# LFO.net
KiCad netlist of a schematic drawn in EAGLE
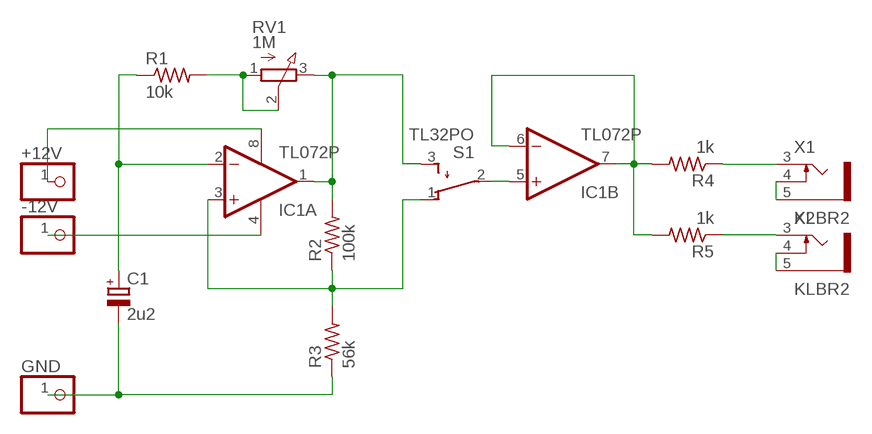
[diagram p0: schematic, sheet 1]

(export (version "E")
  (design (tool "Eeschema 10.0.6"))
  (components
    (comp (ref "+12V")
      (value "PINHD-1X1")
      (footprint "eagle-import:1X01")
      (libsource (lib "eagle-import") (part "PINHD-1X1"))
    )
    (comp (ref "-12V")
      (value "PINHD-1X1")
      (footprint "eagle-import:1X01")
      (libsource (lib "eagle-import") (part "PINHD-1X1"))
    )
    (comp (ref "C1")
      (value "2u2")
      (footprint "eagle-import:E2,5-6E")
      (libsource (lib "eagle-import") (part "CPOL-EUE2,5-6E"))
    )
    (comp (ref "GND")
      (value "PINHD-1X1")
      (footprint "eagle-import:1X01")
      (libsource (lib "eagle-import") (part "PINHD-1X1"))
    )
    (comp (ref "IC1")
      (value "TL072P")
      (footprint "eagle-import:DIL08")
      (libsource (lib "eagle-import") (part "TL072P"))
    )
    (comp (ref "R1")
      (value "10k")
      (footprint "eagle-import:0204_7")
      (libsource (lib "eagle-import") (part "R-US_0204/7"))
    )
    (comp (ref "R2")
      (value "100k")
      (footprint "eagle-import:0204_7")
      (libsource (lib "eagle-import") (part "R-US_0204/7"))
    )
    (comp (ref "R3")
      (value "56k")
      (footprint "eagle-import:0204_7")
      (libsource (lib "eagle-import") (part "R-US_0204/7"))
    )
    (comp (ref "R4")
      (value "1k")
      (footprint "eagle-import:0204_7")
      (libsource (lib "eagle-import") (part "R-US_0204/7"))
    )
    (comp (ref "R5")
      (value "1k")
      (footprint "eagle-import:0204_7")
      (libsource (lib "eagle-import") (part "R-US_0204/7"))
    )
    (comp (ref "RV1")
      (value "1M")
      (footprint "eagle-import:3RP_1610N")
      (libsource (lib "eagle-import") (part "3RP/1610N"))
    )
    (comp (ref "S1")
      (value "TL32PO")
      (footprint "eagle-import:TL3XPO")
      (libsource (lib "eagle-import") (part "TL32PO"))
    )
    (comp (ref "X1")
      (value "KLBR2")
      (footprint "eagle-import:KLBR2")
      (libsource (lib "eagle-import") (part "KLBR?2"))
    )
    (comp (ref "X2")
      (value "KLBR2")
      (footprint "eagle-import:KLBR2")
      (libsource (lib "eagle-import") (part "KLBR?2"))
    )
  )
  (nets
    (net (code "1") (name "Net-(C1-Pad-)") (class "Default")
      (node (ref "C1") (pin "-") (pinfunction "-_-") (pintype "passive"))
      (node (ref "GND") (pin "1") (pinfunction "1_1") (pintype "passive"))
      (node (ref "R3") (pin "1") (pinfunction "1_1") (pintype "passive"))
    )
    (net (code "2") (name "Net-(IC1A-+IN)") (class "Default")
      (node (ref "IC1") (pin "3") (pinfunction "+IN_3") (pintype "input"))
      (node (ref "R2") (pin "1") (pinfunction "1_1") (pintype "passive"))
      (node (ref "R3") (pin "2") (pinfunction "2_2") (pintype "passive"))
      (node (ref "S1") (pin "1") (pinfunction "O_1") (pintype "passive"))
    )
    (net (code "3") (name "Net-(IC1A--IN)") (class "Default")
      (node (ref "C1") (pin "+") (pinfunction "+_+") (pintype "passive"))
      (node (ref "IC1") (pin "2") (pinfunction "-IN_2") (pintype "input"))
      (node (ref "R1") (pin "1") (pinfunction "1_1") (pintype "passive"))
    )
    (net (code "4") (name "Net-(IC1A-OUT)") (class "Default")
      (node (ref "IC1") (pin "1") (pinfunction "OUT_1") (pintype "output"))
      (node (ref "R2") (pin "2") (pinfunction "2_2") (pintype "passive"))
      (node (ref "RV1") (pin "3") (pinfunction "E_3") (pintype "passive"))
      (node (ref "S1") (pin "3") (pinfunction "S_3") (pintype "passive"))
    )
    (net (code "5") (name "Net-(IC1B-+IN)") (class "Default")
      (node (ref "IC1") (pin "5") (pinfunction "+IN_5") (pintype "input"))
      (node (ref "S1") (pin "2") (pinfunction "P_2") (pintype "passive"))
    )
    (net (code "6") (name "Net-(IC1B--IN)") (class "Default")
      (node (ref "IC1") (pin "6") (pinfunction "-IN_6") (pintype "input"))
      (node (ref "IC1") (pin "7") (pinfunction "OUT_7") (pintype "output"))
      (node (ref "R4") (pin "2") (pinfunction "2_2") (pintype "passive"))
      (node (ref "R5") (pin "2") (pinfunction "2_2") (pintype "passive"))
    )
    (net (code "7") (name "Net-(IC1C-V+)") (class "Default")
      (node (ref "+12V") (pin "1") (pinfunction "1_1") (pintype "passive"))
      (node (ref "IC1") (pin "8") (pinfunction "V+_8") (pintype "power_in"))
    )
    (net (code "8") (name "Net-(IC1C-V-)") (class "Default")
      (node (ref "-12V") (pin "1") (pinfunction "1_1") (pintype "passive"))
      (node (ref "IC1") (pin "4") (pinfunction "V-_4") (pintype "power_in"))
    )
    (net (code "9") (name "Net-(R4-Pad1)") (class "Default")
      (node (ref "R4") (pin "1") (pinfunction "1_1") (pintype "passive"))
      (node (ref "X1") (pin "3") (pinfunction "3_3") (pintype "passive"))
    )
    (net (code "10") (name "Net-(R5-Pad1)") (class "Default")
      (node (ref "R5") (pin "1") (pinfunction "1_1") (pintype "passive"))
      (node (ref "X2") (pin "3") (pinfunction "3_3") (pintype "passive"))
    )
    (net (code "11") (name "Net-(RV1-A)") (class "Default")
      (node (ref "R1") (pin "2") (pinfunction "2_2") (pintype "passive"))
      (node (ref "RV1") (pin "1") (pinfunction "A_1") (pintype "passive"))
      (node (ref "RV1") (pin "2") (pinfunction "S_2") (pintype "passive"))
    )
    (net (code "12") (name "Net-(X1-Pad4)") (class "Default")
      (node (ref "X1") (pin "4") (pinfunction "4_4") (pintype "passive"))
      (node (ref "X1") (pin "5") (pinfunction "5_5") (pintype "passive"))
    )
    (net (code "13") (name "Net-(X2-Pad4)") (class "Default")
      (node (ref "X2") (pin "4") (pinfunction "4_4") (pintype "passive"))
      (node (ref "X2") (pin "5") (pinfunction "5_5") (pintype "passive"))
    )
  )
)
